# asol_v1.net
KiCad netlist of a schematic drawn in EAGLE
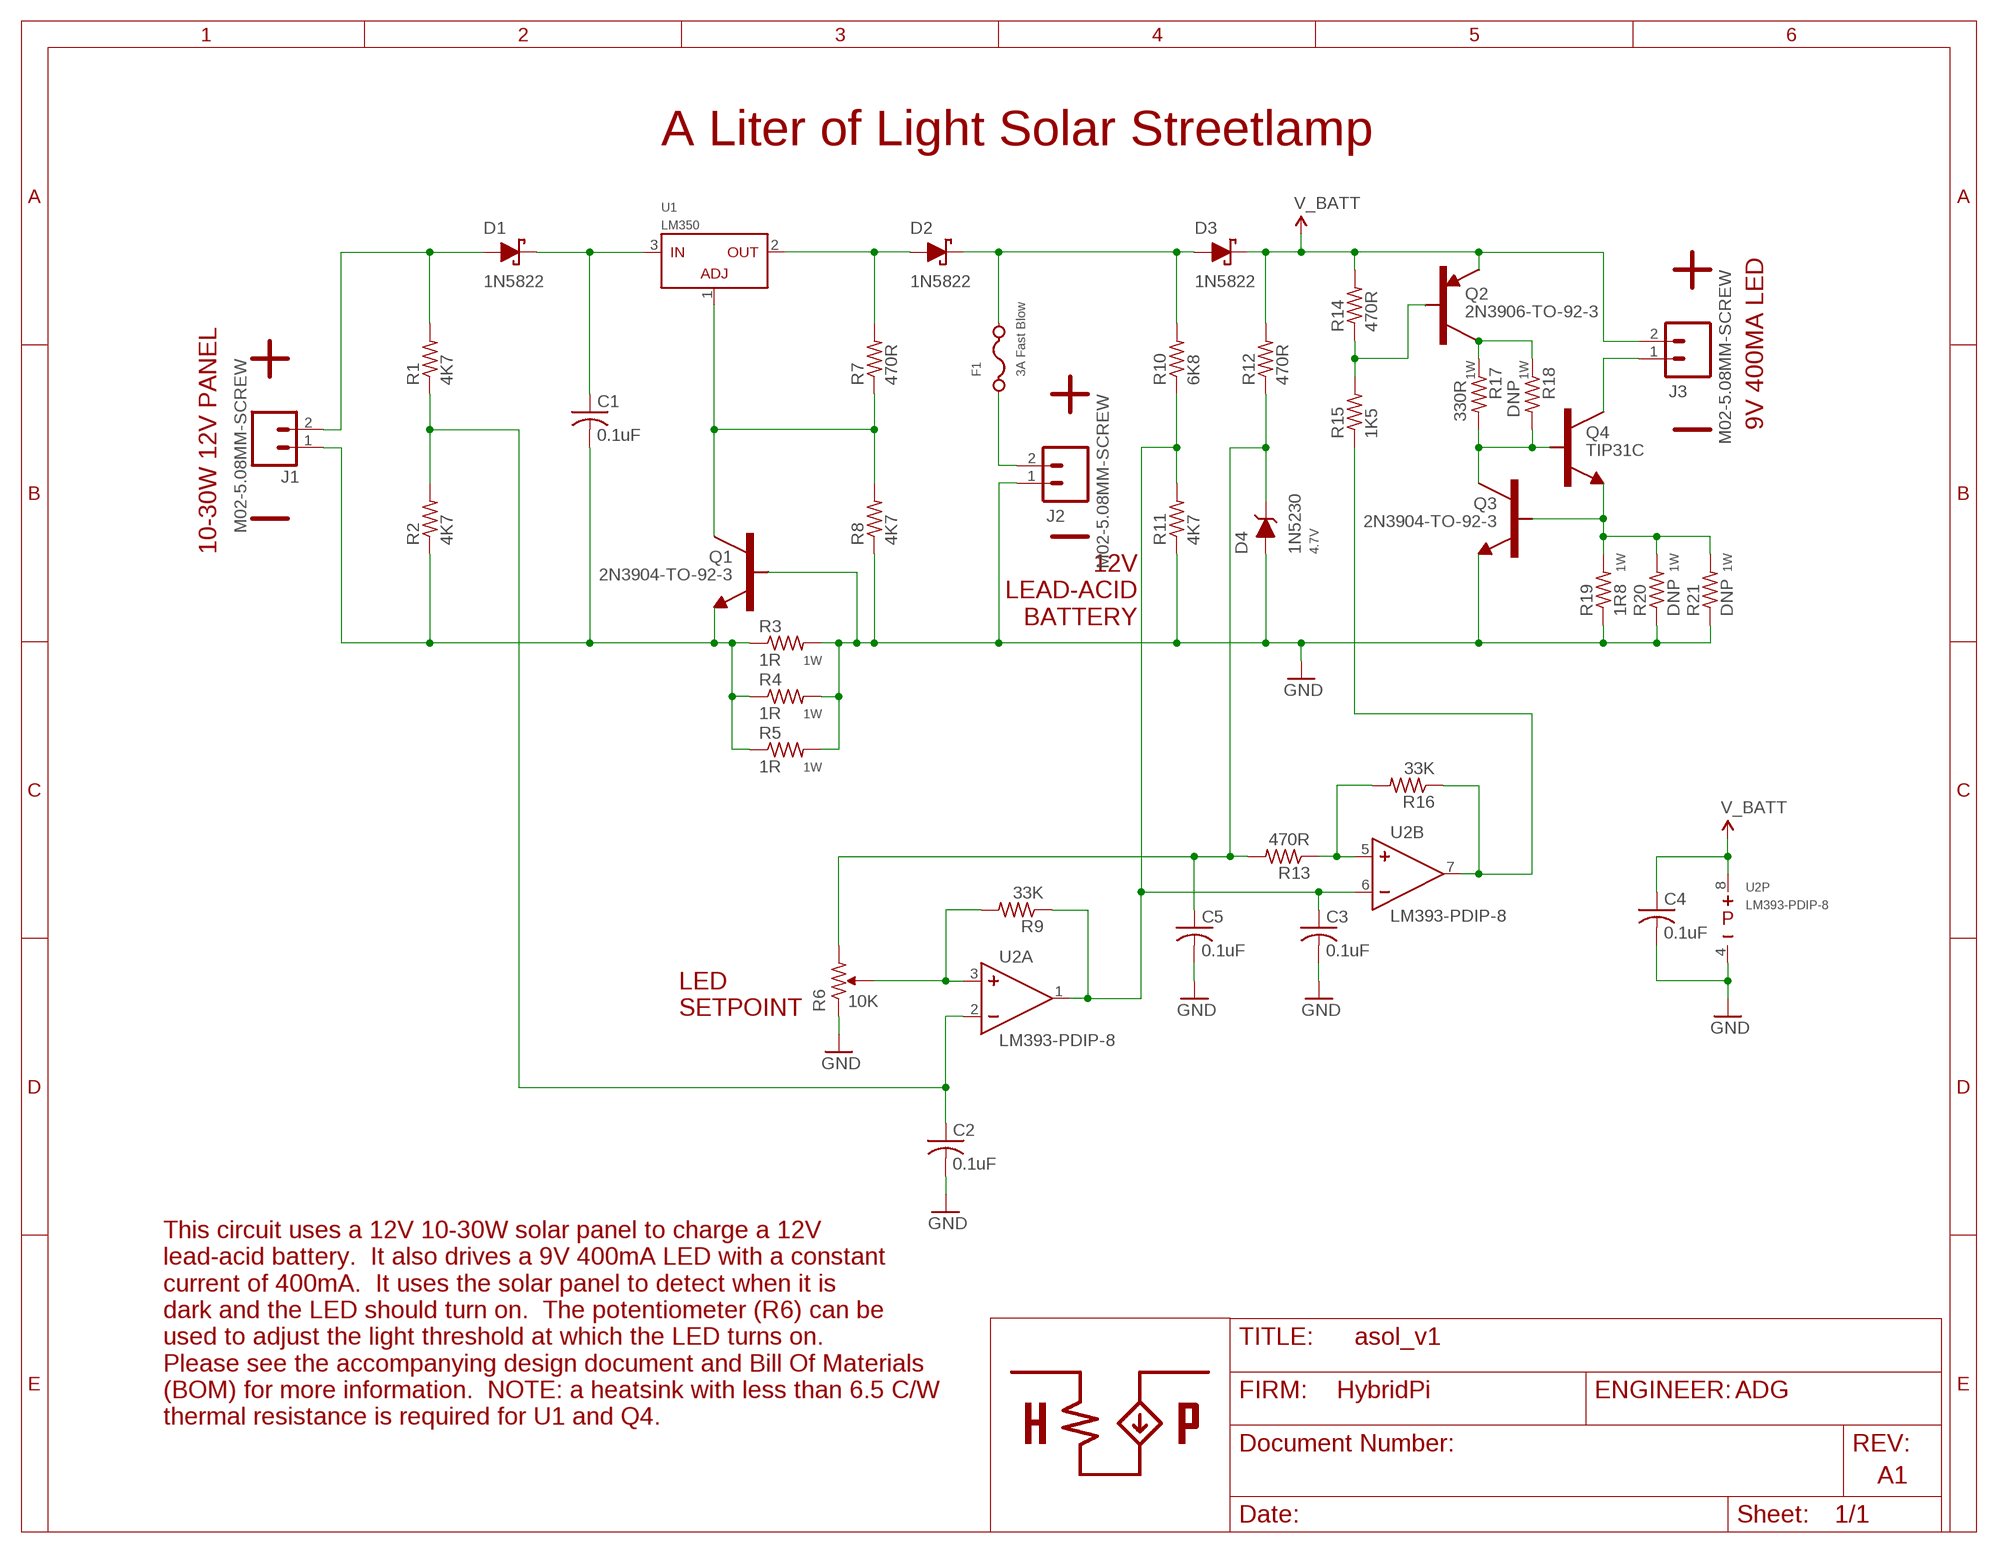
[diagram p0: schematic, sheet 1]

(export (version "E")
  (design (tool "Eeschema 10.0.6"))
  (components
    (comp (ref "C1")
      (value "0.1uF")
      (footprint "eagle-import:C025-025X050")
      (libsource (lib "eagle-import") (part "C-US025-025X050"))
    )
    (comp (ref "C2")
      (value "0.1uF")
      (footprint "eagle-import:C025-025X050")
      (libsource (lib "eagle-import") (part "C-US025-025X050"))
    )
    (comp (ref "C3")
      (value "0.1uF")
      (footprint "eagle-import:C025-025X050")
      (libsource (lib "eagle-import") (part "C-US025-025X050"))
    )
    (comp (ref "C4")
      (value "0.1uF")
      (footprint "eagle-import:C025-025X050")
      (libsource (lib "eagle-import") (part "C-US025-025X050"))
    )
    (comp (ref "C5")
      (value "0.1uF")
      (footprint "eagle-import:C025-025X050")
      (libsource (lib "eagle-import") (part "C-US025-025X050"))
    )
    (comp (ref "D1")
      (value "1N5822")
      (footprint "eagle-import:DO-201AD")
      (libsource (lib "eagle-import") (part "DIODE-SCHOTTKY-DO-201AD"))
    )
    (comp (ref "D2")
      (value "1N5822")
      (footprint "eagle-import:DO-201AD")
      (libsource (lib "eagle-import") (part "DIODE-SCHOTTKY-DO-201AD"))
    )
    (comp (ref "D3")
      (value "1N5822")
      (footprint "eagle-import:DO-201AD")
      (libsource (lib "eagle-import") (part "DIODE-SCHOTTKY-DO-201AD"))
    )
    (comp (ref "D4")
      (value "1N5230")
      (footprint "eagle-import:DO-35")
      (fields (field (name "VOLTAGE") "4.7V"))
      (libsource (lib "eagle-import") (part "DIODE-ZENER-DO-35"))
    )
    (comp (ref "F1")
      (value "3A Fast Blow")
      (footprint "eagle-import:FUSE-5X20MM")
      (libsource (lib "eagle-import") (part "FUSE-CARTRIDGE-5X20MM"))
    )
    (comp (ref "J1")
      (value "M02-5.08MM-SCREW")
      (footprint "eagle-import:SCREW-TERMINAL-5.08MM-1X2")
      (libsource (lib "eagle-import") (part "M02-5.08MM-SCREW"))
    )
    (comp (ref "J2")
      (value "M02-5.08MM-SCREW")
      (footprint "eagle-import:SCREW-TERMINAL-5.08MM-1X2")
      (libsource (lib "eagle-import") (part "M02-5.08MM-SCREW"))
    )
    (comp (ref "J3")
      (value "M02-5.08MM-SCREW")
      (footprint "eagle-import:SCREW-TERMINAL-5.08MM-1X2")
      (libsource (lib "eagle-import") (part "M02-5.08MM-SCREW"))
    )
    (comp (ref "Q1")
      (value "2N3904-TO-92-3")
      (footprint "eagle-import:TO-92-3")
      (libsource (lib "eagle-import") (part "2N3904-TO-92-3"))
    )
    (comp (ref "Q2")
      (value "2N3906-TO-92-3")
      (footprint "eagle-import:TO-92-3")
      (libsource (lib "eagle-import") (part "2N3906-TO-92-3"))
    )
    (comp (ref "Q3")
      (value "2N3904-TO-92-3")
      (footprint "eagle-import:TO-92-3")
      (libsource (lib "eagle-import") (part "2N3904-TO-92-3"))
    )
    (comp (ref "Q4")
      (value "TIP31C")
      (footprint "eagle-import:TO-220-3")
      (libsource (lib "eagle-import") (part "TIP31C"))
    )
    (comp (ref "R1")
      (value "4K7")
      (footprint "eagle-import:0207_12")
      (libsource (lib "eagle-import") (part "R-US_0207/12"))
    )
    (comp (ref "R2")
      (value "4K7")
      (footprint "eagle-import:0207_12")
      (libsource (lib "eagle-import") (part "R-US_0207/12"))
    )
    (comp (ref "R3")
      (value "1R")
      (footprint "eagle-import:0309_12")
      (fields (field (name "POWER") "1W"))
      (libsource (lib "eagle-import") (part "R-US_0309/12"))
    )
    (comp (ref "R4")
      (value "1R")
      (footprint "eagle-import:0309_12")
      (fields (field (name "POWER") "1W"))
      (libsource (lib "eagle-import") (part "R-US_0309/12"))
    )
    (comp (ref "R5")
      (value "1R")
      (footprint "eagle-import:0309_12")
      (fields (field (name "POWER") "1W"))
      (libsource (lib "eagle-import") (part "R-US_0309/12"))
    )
    (comp (ref "R6")
      (value "10K")
      (footprint "eagle-import:POT-PTH-5X10MM")
      (libsource (lib "eagle-import") (part "POT-PTH-5X10MM"))
    )
    (comp (ref "R7")
      (value "470R")
      (footprint "eagle-import:0207_12")
      (libsource (lib "eagle-import") (part "R-US_0207/12"))
    )
    (comp (ref "R8")
      (value "4K7")
      (footprint "eagle-import:0207_12")
      (libsource (lib "eagle-import") (part "R-US_0207/12"))
    )
    (comp (ref "R9")
      (value "33K")
      (footprint "eagle-import:0207_12")
      (libsource (lib "eagle-import") (part "R-US_0207/12"))
    )
    (comp (ref "R10")
      (value "6K8")
      (footprint "eagle-import:0207_12")
      (libsource (lib "eagle-import") (part "R-US_0207/12"))
    )
    (comp (ref "R11")
      (value "4K7")
      (footprint "eagle-import:0207_12")
      (libsource (lib "eagle-import") (part "R-US_0207/12"))
    )
    (comp (ref "R12")
      (value "470R")
      (footprint "eagle-import:0207_12")
      (libsource (lib "eagle-import") (part "R-US_0207/12"))
    )
    (comp (ref "R13")
      (value "470R")
      (footprint "eagle-import:0207_12")
      (libsource (lib "eagle-import") (part "R-US_0207/12"))
    )
    (comp (ref "R14")
      (value "470R")
      (footprint "eagle-import:0207_12")
      (libsource (lib "eagle-import") (part "R-US_0207/12"))
    )
    (comp (ref "R15")
      (value "1K5")
      (footprint "eagle-import:0207_12")
      (libsource (lib "eagle-import") (part "R-US_0207/12"))
    )
    (comp (ref "R16")
      (value "33K")
      (footprint "eagle-import:0207_12")
      (libsource (lib "eagle-import") (part "R-US_0207/12"))
    )
    (comp (ref "R17")
      (value "330R")
      (footprint "eagle-import:0309_12")
      (fields (field (name "POWER") "1W"))
      (libsource (lib "eagle-import") (part "R-US_0309/12"))
    )
    (comp (ref "R18")
      (value "DNP")
      (footprint "eagle-import:0309_12")
      (fields (field (name "POWER") "1W"))
      (libsource (lib "eagle-import") (part "R-US_0309/12"))
    )
    (comp (ref "R19")
      (value "1R8")
      (footprint "eagle-import:0309_12")
      (fields (field (name "POWER") "1W"))
      (libsource (lib "eagle-import") (part "R-US_0309/12"))
    )
    (comp (ref "R20")
      (value "DNP")
      (footprint "eagle-import:0309_12")
      (fields (field (name "POWER") "1W"))
      (libsource (lib "eagle-import") (part "R-US_0309/12"))
    )
    (comp (ref "R21")
      (value "DNP")
      (footprint "eagle-import:0309_12")
      (fields (field (name "POWER") "1W"))
      (libsource (lib "eagle-import") (part "R-US_0309/12"))
    )
    (comp (ref "U1")
      (value "LM350")
      (footprint "eagle-import:TO-220-3")
      (libsource (lib "eagle-import") (part "LM350"))
    )
    (comp (ref "U2")
      (value "LM393-PDIP-8")
      (footprint "eagle-import:PDIP-8")
      (fields (field (name "VENDOR") "DIGIKEY") (field (name "VENDOR_PN") "296-1398-5-ND"))
      (libsource (lib "eagle-import") (part "LM393-PDIP-8"))
    )
  )
  (nets
    (net (code "1") (name "GND") (class "Default")
      (node (ref "C2") (pin "2") (pinfunction "2_2") (pintype "passive"))
      (node (ref "C3") (pin "2") (pinfunction "2_2") (pintype "passive"))
      (node (ref "C4") (pin "2") (pinfunction "2_2") (pintype "passive"))
      (node (ref "C5") (pin "2") (pinfunction "2_2") (pintype "passive"))
      (node (ref "D4") (pin "P$2") (pinfunction "A_P$2") (pintype "bidirectional"))
      (node (ref "J2") (pin "1") (pinfunction "1_1") (pintype "passive"))
      (node (ref "Q1") (pin "2") (pinfunction "B_2") (pintype "bidirectional"))
      (node (ref "Q3") (pin "1") (pinfunction "E_1") (pintype "bidirectional"))
      (node (ref "R11") (pin "1") (pinfunction "1_1") (pintype "passive"))
      (node (ref "R19") (pin "1") (pinfunction "1_1") (pintype "passive"))
      (node (ref "R20") (pin "1") (pinfunction "1_1") (pintype "passive"))
      (node (ref "R21") (pin "1") (pinfunction "1_1") (pintype "passive"))
      (node (ref "R3") (pin "2") (pinfunction "2_2") (pintype "passive"))
      (node (ref "R4") (pin "2") (pinfunction "2_2") (pintype "passive"))
      (node (ref "R5") (pin "2") (pinfunction "2_2") (pintype "passive"))
      (node (ref "R6") (pin "1") (pinfunction "1_1") (pintype "passive"))
      (node (ref "R8") (pin "1") (pinfunction "1_1") (pintype "passive"))
      (node (ref "U2") (pin "4") (pinfunction "NEG_4") (pintype "bidirectional"))
    )
    (net (code "2") (name "Net-(D1-A)") (class "Default")
      (node (ref "D1") (pin "P$2") (pinfunction "A_P$2") (pintype "bidirectional"))
      (node (ref "J1") (pin "2") (pinfunction "2_2") (pintype "passive"))
      (node (ref "R1") (pin "2") (pinfunction "2_2") (pintype "passive"))
    )
    (net (code "3") (name "Net-(D1-C)") (class "Default")
      (node (ref "C1") (pin "1") (pinfunction "1_1") (pintype "passive"))
      (node (ref "D1") (pin "P$1") (pinfunction "C_P$1") (pintype "bidirectional"))
      (node (ref "U1") (pin "3") (pinfunction "IN_3") (pintype "bidirectional"))
    )
    (net (code "4") (name "Net-(D2-A)") (class "Default")
      (node (ref "D2") (pin "P$2") (pinfunction "A_P$2") (pintype "bidirectional"))
      (node (ref "R7") (pin "2") (pinfunction "2_2") (pintype "passive"))
      (node (ref "U1") (pin "2") (pinfunction "OUT_2") (pintype "bidirectional"))
    )
    (net (code "5") (name "Net-(D2-C)") (class "Default")
      (node (ref "D2") (pin "P$1") (pinfunction "C_P$1") (pintype "bidirectional"))
      (node (ref "D3") (pin "P$2") (pinfunction "A_P$2") (pintype "bidirectional"))
      (node (ref "F1") (pin "3") (pinfunction "2_3") (pintype "bidirectional"))
      (node (ref "F1") (pin "4") (pinfunction "2_4") (pintype "bidirectional"))
      (node (ref "R10") (pin "2") (pinfunction "2_2") (pintype "passive"))
    )
    (net (code "6") (name "Net-(D4-C)") (class "Default")
      (node (ref "C5") (pin "1") (pinfunction "1_1") (pintype "passive"))
      (node (ref "D4") (pin "P$1") (pinfunction "C_P$1") (pintype "bidirectional"))
      (node (ref "R12") (pin "1") (pinfunction "1_1") (pintype "passive"))
      (node (ref "R13") (pin "2") (pinfunction "2_2") (pintype "passive"))
      (node (ref "R6") (pin "3") (pinfunction "3_3") (pintype "passive"))
    )
    (net (code "7") (name "Net-(F1-1-Pad2)") (class "Default")
      (node (ref "F1") (pin "1") (pinfunction "1_1") (pintype "bidirectional"))
      (node (ref "F1") (pin "2") (pinfunction "1_2") (pintype "bidirectional"))
      (node (ref "J2") (pin "2") (pinfunction "2_2") (pintype "passive"))
    )
    (net (code "8") (name "Net-(Q1-C)") (class "Default")
      (node (ref "Q1") (pin "3") (pinfunction "C_3") (pintype "bidirectional"))
      (node (ref "R7") (pin "1") (pinfunction "1_1") (pintype "passive"))
      (node (ref "R8") (pin "2") (pinfunction "2_2") (pintype "passive"))
      (node (ref "U1") (pin "1") (pinfunction "ADJ_1") (pintype "bidirectional"))
    )
    (net (code "9") (name "Net-(Q1-E)") (class "Default")
      (node (ref "C1") (pin "2") (pinfunction "2_2") (pintype "passive"))
      (node (ref "J1") (pin "1") (pinfunction "1_1") (pintype "passive"))
      (node (ref "Q1") (pin "1") (pinfunction "E_1") (pintype "bidirectional"))
      (node (ref "R2") (pin "1") (pinfunction "1_1") (pintype "passive"))
      (node (ref "R3") (pin "1") (pinfunction "1_1") (pintype "passive"))
      (node (ref "R4") (pin "1") (pinfunction "1_1") (pintype "passive"))
      (node (ref "R5") (pin "1") (pinfunction "1_1") (pintype "passive"))
    )
    (net (code "10") (name "Net-(Q2-B)") (class "Default")
      (node (ref "Q2") (pin "2") (pinfunction "B_2") (pintype "bidirectional"))
      (node (ref "R14") (pin "1") (pinfunction "1_1") (pintype "passive"))
      (node (ref "R15") (pin "2") (pinfunction "2_2") (pintype "passive"))
    )
    (net (code "11") (name "Net-(Q2-C)") (class "Default")
      (node (ref "Q2") (pin "3") (pinfunction "C_3") (pintype "bidirectional"))
      (node (ref "R17") (pin "1") (pinfunction "1_1") (pintype "passive"))
      (node (ref "R18") (pin "1") (pinfunction "1_1") (pintype "passive"))
    )
    (net (code "12") (name "Net-(Q3-B)") (class "Default")
      (node (ref "Q3") (pin "2") (pinfunction "B_2") (pintype "bidirectional"))
      (node (ref "Q4") (pin "3") (pinfunction "E_3") (pintype "bidirectional"))
      (node (ref "R19") (pin "2") (pinfunction "2_2") (pintype "passive"))
      (node (ref "R20") (pin "2") (pinfunction "2_2") (pintype "passive"))
      (node (ref "R21") (pin "2") (pinfunction "2_2") (pintype "passive"))
    )
    (net (code "13") (name "Net-(Q3-C)") (class "Default")
      (node (ref "Q3") (pin "3") (pinfunction "C_3") (pintype "bidirectional"))
      (node (ref "Q4") (pin "1") (pinfunction "B_1") (pintype "bidirectional"))
      (node (ref "R17") (pin "2") (pinfunction "2_2") (pintype "passive"))
      (node (ref "R18") (pin "2") (pinfunction "2_2") (pintype "passive"))
    )
    (net (code "14") (name "Net-(Q4-C)") (class "Default")
      (node (ref "J3") (pin "1") (pinfunction "1_1") (pintype "passive"))
      (node (ref "Q4") (pin "2") (pinfunction "C_2") (pintype "bidirectional"))
    )
    (net (code "15") (name "Net-(U2A-IN+)") (class "Default")
      (node (ref "R6") (pin "2") (pinfunction "2_2") (pintype "passive"))
      (node (ref "R9") (pin "2") (pinfunction "2_2") (pintype "passive"))
      (node (ref "U2") (pin "3") (pinfunction "IN+_3") (pintype "bidirectional"))
    )
    (net (code "16") (name "Net-(U2A-IN-)") (class "Default")
      (node (ref "C2") (pin "1") (pinfunction "1_1") (pintype "passive"))
      (node (ref "R1") (pin "1") (pinfunction "1_1") (pintype "passive"))
      (node (ref "R2") (pin "2") (pinfunction "2_2") (pintype "passive"))
      (node (ref "U2") (pin "2") (pinfunction "IN-_2") (pintype "bidirectional"))
    )
    (net (code "17") (name "Net-(U2A-OUT)") (class "Default")
      (node (ref "C3") (pin "1") (pinfunction "1_1") (pintype "passive"))
      (node (ref "R10") (pin "1") (pinfunction "1_1") (pintype "passive"))
      (node (ref "R11") (pin "2") (pinfunction "2_2") (pintype "passive"))
      (node (ref "R9") (pin "1") (pinfunction "1_1") (pintype "passive"))
      (node (ref "U2") (pin "1") (pinfunction "OUT_1") (pintype "bidirectional"))
      (node (ref "U2") (pin "6") (pinfunction "IN-_6") (pintype "bidirectional"))
    )
    (net (code "18") (name "Net-(U2B-IN+)") (class "Default")
      (node (ref "R13") (pin "1") (pinfunction "1_1") (pintype "passive"))
      (node (ref "R16") (pin "2") (pinfunction "2_2") (pintype "passive"))
      (node (ref "U2") (pin "5") (pinfunction "IN+_5") (pintype "bidirectional"))
    )
    (net (code "19") (name "Net-(U2B-OUT)") (class "Default")
      (node (ref "R15") (pin "1") (pinfunction "1_1") (pintype "passive"))
      (node (ref "R16") (pin "1") (pinfunction "1_1") (pintype "passive"))
      (node (ref "U2") (pin "7") (pinfunction "OUT_7") (pintype "bidirectional"))
    )
    (net (code "20") (name "V_BATT") (class "Default")
      (node (ref "C4") (pin "1") (pinfunction "1_1") (pintype "passive"))
      (node (ref "D3") (pin "P$1") (pinfunction "C_P$1") (pintype "bidirectional"))
      (node (ref "J3") (pin "2") (pinfunction "2_2") (pintype "passive"))
      (node (ref "Q2") (pin "1") (pinfunction "E_1") (pintype "bidirectional"))
      (node (ref "R12") (pin "2") (pinfunction "2_2") (pintype "passive"))
      (node (ref "R14") (pin "2") (pinfunction "2_2") (pintype "passive"))
      (node (ref "U2") (pin "8") (pinfunction "POS_8") (pintype "bidirectional"))
    )
  )
)
